# MicroMultimeter_MCU_Sch.net
KiCad netlist of a schematic drawn in Altium Designer
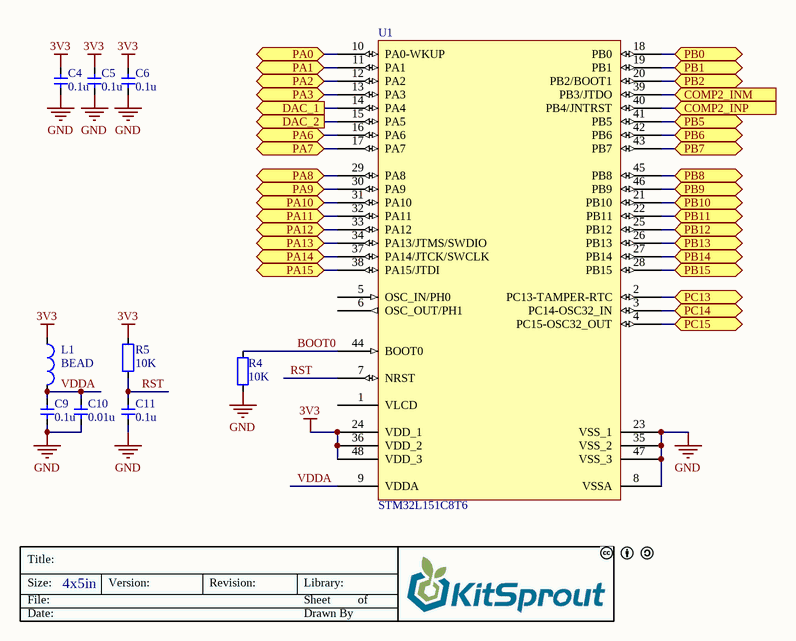
[diagram p0: MicroMultimeter_MCU_Sch.SchDoc]

(export (version "E")
  (design (tool "Eeschema 10.0.6"))
  (components
    (comp (ref "C4")
      (value "0.1u")
      (footprint "CAP_0603")
      (description "Capacitor")
      (fields (field (name "Comment") "Cap_0603"))
      (libsource (lib "SCH_Passive") (part "Cap_0603"))
    )
    (comp (ref "C5")
      (value "0.1u")
      (footprint "CAP_0603")
      (description "Capacitor")
      (fields (field (name "Comment") "Cap_0603"))
      (libsource (lib "SCH_Passive") (part "Cap_0603"))
    )
    (comp (ref "C6")
      (value "0.1u")
      (footprint "CAP_0603")
      (description "Capacitor")
      (fields (field (name "Comment") "Cap_0603"))
      (libsource (lib "SCH_Passive") (part "Cap_0603"))
    )
    (comp (ref "C9")
      (value "0.1u")
      (footprint "CAP_0603")
      (description "Capacitor")
      (fields (field (name "Comment") "Cap_0603"))
      (libsource (lib "SCH_Passive") (part "Cap_0603"))
    )
    (comp (ref "C10")
      (value "0.01u")
      (footprint "CAP_0603")
      (description "Capacitor")
      (fields (field (name "Comment") "Cap_0603"))
      (libsource (lib "SCH_Passive") (part "Cap_0603"))
    )
    (comp (ref "C11")
      (value "0.1u")
      (footprint "CAP_0603")
      (description "Capacitor")
      (fields (field (name "Comment") "Cap_0603"))
      (libsource (lib "SCH_Passive") (part "Cap_0603"))
    )
    (comp (ref "L1")
      (value "BEAD")
      (footprint "PCB_PassiveInd:IND_0603")
      (description "Inductor")
      (fields (field (name "Comment") "Ind_0603"))
      (libsource (lib "SCH_Passive") (part "Ind_0603"))
    )
    (comp (ref "R4")
      (value "10K")
      (footprint "RES_0603")
      (description "Resistor")
      (fields (field (name "Comment") "Res_0603"))
      (libsource (lib "SCH_Passive") (part "Res_0603"))
    )
    (comp (ref "R5")
      (value "10K")
      (footprint "RES_0603")
      (description "Resistor")
      (fields (field (name "Comment") "Res_0603"))
      (libsource (lib "SCH_Passive") (part "Res_0603"))
    )
    (comp (ref "U1")
      (value "STM32L151C8T6")
      (footprint "LQFP48_N")
      (description "STM32 ARM-based 32-bit MCU with 64 Kbytes Flash, 48-pin LQFP, Industrial Temperature")
      (fields (field (name "PUBLISHER") "Altium Limited"))
      (libsource (lib "ST Microcontroller 32-Bit STM32") (part "STM32L151C8T6"))
    )
  )
  (nets
    (net (code "1") (name "/BOOT0") (class "Default")
      (node (ref "R4") (pin "2") (pinfunction "2_2") (pintype "passive"))
      (node (ref "U1") (pin "44") (pinfunction "BOOT0_44") (pintype "input"))
    )
    (net (code "2") (name "/COMP2_INM") (class "Default")
      (node (ref "U1") (pin "39") (pinfunction "PB3/JTDO_39") (pintype "bidirectional"))
    )
    (net (code "3") (name "/COMP2_INP") (class "Default")
      (node (ref "U1") (pin "40") (pinfunction "PB4/JNTRST_40") (pintype "bidirectional"))
    )
    (net (code "4") (name "/DAC_1") (class "Default")
      (node (ref "U1") (pin "14") (pinfunction "PA4_14") (pintype "bidirectional"))
    )
    (net (code "5") (name "/DAC_2") (class "Default")
      (node (ref "U1") (pin "15") (pinfunction "PA5_15") (pintype "bidirectional"))
    )
    (net (code "6") (name "/PA0") (class "Default")
      (node (ref "U1") (pin "10") (pinfunction "PA0-WKUP_10") (pintype "bidirectional"))
    )
    (net (code "7") (name "/PA1") (class "Default")
      (node (ref "U1") (pin "11") (pinfunction "PA1_11") (pintype "bidirectional"))
    )
    (net (code "8") (name "/PA2") (class "Default")
      (node (ref "U1") (pin "12") (pinfunction "PA2_12") (pintype "bidirectional"))
    )
    (net (code "9") (name "/PA3") (class "Default")
      (node (ref "U1") (pin "13") (pinfunction "PA3_13") (pintype "bidirectional"))
    )
    (net (code "10") (name "/PA6") (class "Default")
      (node (ref "U1") (pin "16") (pinfunction "PA6_16") (pintype "bidirectional"))
    )
    (net (code "11") (name "/PA7") (class "Default")
      (node (ref "U1") (pin "17") (pinfunction "PA7_17") (pintype "bidirectional"))
    )
    (net (code "12") (name "/PA8") (class "Default")
      (node (ref "U1") (pin "29") (pinfunction "PA8_29") (pintype "bidirectional"))
    )
    (net (code "13") (name "/PA9") (class "Default")
      (node (ref "U1") (pin "30") (pinfunction "PA9_30") (pintype "bidirectional"))
    )
    (net (code "14") (name "/PA10") (class "Default")
      (node (ref "U1") (pin "31") (pinfunction "PA10_31") (pintype "bidirectional"))
    )
    (net (code "15") (name "/PA11") (class "Default")
      (node (ref "U1") (pin "32") (pinfunction "PA11_32") (pintype "bidirectional"))
    )
    (net (code "16") (name "/PA12") (class "Default")
      (node (ref "U1") (pin "33") (pinfunction "PA12_33") (pintype "bidirectional"))
    )
    (net (code "17") (name "/PA13") (class "Default")
      (node (ref "U1") (pin "34") (pinfunction "PA13/JTMS/SWDIO_34") (pintype "bidirectional"))
    )
    (net (code "18") (name "/PA14") (class "Default")
      (node (ref "U1") (pin "37") (pinfunction "PA14/JTCK/SWCLK_37") (pintype "bidirectional"))
    )
    (net (code "19") (name "/PA15") (class "Default")
      (node (ref "U1") (pin "38") (pinfunction "PA15/JTDI_38") (pintype "bidirectional"))
    )
    (net (code "20") (name "/PB0") (class "Default")
      (node (ref "U1") (pin "18") (pinfunction "PB0_18") (pintype "bidirectional"))
    )
    (net (code "21") (name "/PB1") (class "Default")
      (node (ref "U1") (pin "19") (pinfunction "PB1_19") (pintype "bidirectional"))
    )
    (net (code "22") (name "/PB2") (class "Default")
      (node (ref "U1") (pin "20") (pinfunction "PB2/BOOT1_20") (pintype "bidirectional"))
    )
    (net (code "23") (name "/PB5") (class "Default")
      (node (ref "U1") (pin "41") (pinfunction "PB5_41") (pintype "bidirectional"))
    )
    (net (code "24") (name "/PB6") (class "Default")
      (node (ref "U1") (pin "42") (pinfunction "PB6_42") (pintype "bidirectional"))
    )
    (net (code "25") (name "/PB7") (class "Default")
      (node (ref "U1") (pin "43") (pinfunction "PB7_43") (pintype "bidirectional"))
    )
    (net (code "26") (name "/PB8") (class "Default")
      (node (ref "U1") (pin "45") (pinfunction "PB8_45") (pintype "bidirectional"))
    )
    (net (code "27") (name "/PB9") (class "Default")
      (node (ref "U1") (pin "46") (pinfunction "PB9_46") (pintype "bidirectional"))
    )
    (net (code "28") (name "/PB10") (class "Default")
      (node (ref "U1") (pin "21") (pinfunction "PB10_21") (pintype "bidirectional"))
    )
    (net (code "29") (name "/PB11") (class "Default")
      (node (ref "U1") (pin "22") (pinfunction "PB11_22") (pintype "bidirectional"))
    )
    (net (code "30") (name "/PB12") (class "Default")
      (node (ref "U1") (pin "25") (pinfunction "PB12_25") (pintype "bidirectional"))
    )
    (net (code "31") (name "/PB13") (class "Default")
      (node (ref "U1") (pin "26") (pinfunction "PB13_26") (pintype "bidirectional"))
    )
    (net (code "32") (name "/PB14") (class "Default")
      (node (ref "U1") (pin "27") (pinfunction "PB14_27") (pintype "bidirectional"))
    )
    (net (code "33") (name "/PB15") (class "Default")
      (node (ref "U1") (pin "28") (pinfunction "PB15_28") (pintype "bidirectional"))
    )
    (net (code "34") (name "/PC13") (class "Default")
      (node (ref "U1") (pin "2") (pinfunction "PC13-TAMPER-RTC_2") (pintype "bidirectional"))
    )
    (net (code "35") (name "/PC14") (class "Default")
      (node (ref "U1") (pin "3") (pinfunction "PC14-OSC32_IN_3") (pintype "bidirectional"))
    )
    (net (code "36") (name "/PC15") (class "Default")
      (node (ref "U1") (pin "4") (pinfunction "PC15-OSC32_OUT_4") (pintype "bidirectional"))
    )
    (net (code "37") (name "/RST") (class "Default")
      (node (ref "C11") (pin "2") (pinfunction "2_2") (pintype "passive"))
      (node (ref "R5") (pin "1") (pinfunction "1_1") (pintype "passive"))
      (node (ref "U1") (pin "7") (pinfunction "NRST_7") (pintype "bidirectional"))
    )
    (net (code "38") (name "/VDDA") (class "Default")
      (node (ref "C10") (pin "2") (pinfunction "2_2") (pintype "passive"))
      (node (ref "C9") (pin "2") (pinfunction "2_2") (pintype "passive"))
      (node (ref "L1") (pin "2") (pinfunction "2_2") (pintype "passive"))
      (node (ref "U1") (pin "9") (pinfunction "VDDA_9") (pintype "power_in"))
    )
    (net (code "39") (name "3V3") (class "Default")
      (node (ref "C4") (pin "2") (pinfunction "2_2") (pintype "passive"))
      (node (ref "C5") (pin "2") (pinfunction "2_2") (pintype "passive"))
      (node (ref "C6") (pin "2") (pinfunction "2_2") (pintype "passive"))
      (node (ref "L1") (pin "1") (pinfunction "1_1") (pintype "passive"))
      (node (ref "R5") (pin "2") (pinfunction "2_2") (pintype "passive"))
      (node (ref "U1") (pin "24") (pinfunction "VDD_1_24") (pintype "power_in"))
      (node (ref "U1") (pin "36") (pinfunction "VDD_2_36") (pintype "power_in"))
      (node (ref "U1") (pin "48") (pinfunction "VDD_3_48") (pintype "power_in"))
    )
    (net (code "40") (name "GND") (class "Default")
      (node (ref "C10") (pin "1") (pinfunction "1_1") (pintype "passive"))
      (node (ref "C11") (pin "1") (pinfunction "1_1") (pintype "passive"))
      (node (ref "C4") (pin "1") (pinfunction "1_1") (pintype "passive"))
      (node (ref "C5") (pin "1") (pinfunction "1_1") (pintype "passive"))
      (node (ref "C6") (pin "1") (pinfunction "1_1") (pintype "passive"))
      (node (ref "C9") (pin "1") (pinfunction "1_1") (pintype "passive"))
      (node (ref "R4") (pin "1") (pinfunction "1_1") (pintype "passive"))
      (node (ref "U1") (pin "23") (pinfunction "VSS_1_23") (pintype "power_in"))
      (node (ref "U1") (pin "35") (pinfunction "VSS_2_35") (pintype "power_in"))
      (node (ref "U1") (pin "47") (pinfunction "VSS_3_47") (pintype "power_in"))
      (node (ref "U1") (pin "8") (pinfunction "VSSA_8") (pintype "power_in"))
    )
    (net (code "41") (name "unconnected-(U1-OSC_IN{slash}PH0-Pad5)") (class "Default")
      (node (ref "U1") (pin "5") (pinfunction "OSC_IN/PH0_5") (pintype "input"))
    )
    (net (code "42") (name "unconnected-(U1-OSC_OUT{slash}PH1-Pad6)") (class "Default")
      (node (ref "U1") (pin "6") (pinfunction "OSC_OUT/PH1_6") (pintype "output"))
    )
    (net (code "43") (name "unconnected-(U1-VLCD-Pad1)") (class "Default")
      (node (ref "U1") (pin "1") (pinfunction "VLCD_1") (pintype "power_in"))
    )
  )
)
